# ADC_Analog_Input_Scaler_UPDATED2018.net
KiCad netlist of a schematic drawn in EAGLE
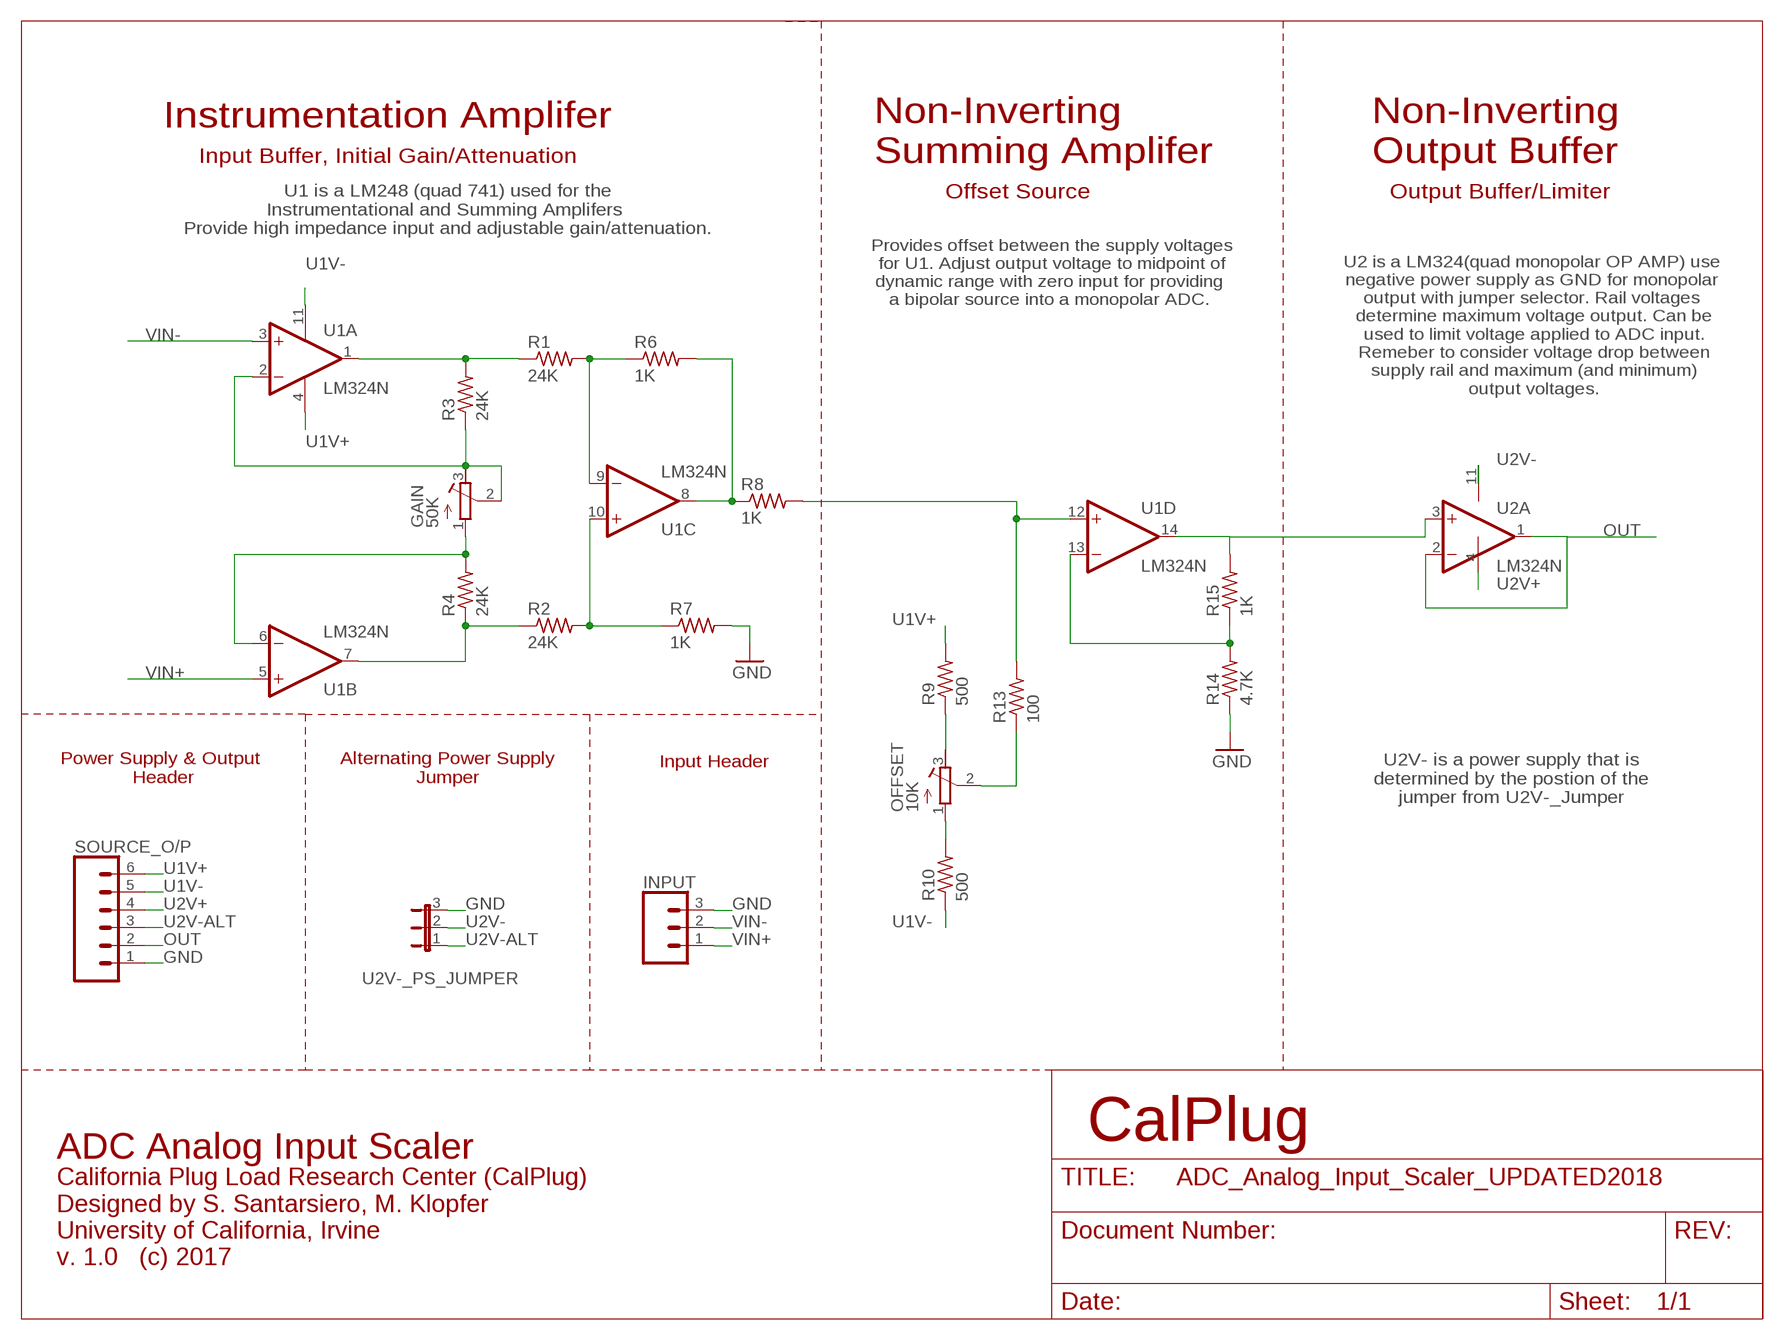
[diagram p0: schematic, sheet 1]

(export (version "E")
  (design (tool "Eeschema 10.0.6"))
  (components
    (comp (ref "GAIN")
      (value "50K")
      (footprint "eagle-import:RTRIM3296W")
      (libsource (lib "eagle-import") (part "R-TRIMM3296W"))
    )
    (comp (ref "INPUT")
      (value "CONN_03")
      (footprint "eagle-import:1X03")
      (libsource (lib "eagle-import") (part "CONN_03"))
    )
    (comp (ref "OFFSET")
      (value "10K")
      (footprint "eagle-import:RTRIM3296W")
      (libsource (lib "eagle-import") (part "R-TRIMM3296W"))
    )
    (comp (ref "R1")
      (value "24K")
      (footprint "eagle-import:R1210")
      (libsource (lib "eagle-import") (part "R-US_R1210"))
    )
    (comp (ref "R2")
      (value "24K")
      (footprint "eagle-import:R1210")
      (libsource (lib "eagle-import") (part "R-US_R1210"))
    )
    (comp (ref "R3")
      (value "24K")
      (footprint "eagle-import:R1210")
      (libsource (lib "eagle-import") (part "R-US_R1210"))
    )
    (comp (ref "R4")
      (value "24K")
      (footprint "eagle-import:R1210")
      (libsource (lib "eagle-import") (part "R-US_R1210"))
    )
    (comp (ref "R6")
      (value "1K")
      (footprint "eagle-import:R1210")
      (libsource (lib "eagle-import") (part "R-US_R1210"))
    )
    (comp (ref "R7")
      (value "1K")
      (footprint "eagle-import:R1210")
      (libsource (lib "eagle-import") (part "R-US_R1210"))
    )
    (comp (ref "R8")
      (value "1K")
      (footprint "eagle-import:R1210")
      (libsource (lib "eagle-import") (part "R-US_R1210"))
    )
    (comp (ref "R9")
      (value "500")
      (footprint "eagle-import:R1206")
      (libsource (lib "eagle-import") (part "R-US_R1206"))
    )
    (comp (ref "R10")
      (value "500")
      (footprint "eagle-import:R1206")
      (libsource (lib "eagle-import") (part "R-US_R1206"))
    )
    (comp (ref "R13")
      (value "100")
      (footprint "eagle-import:R1210")
      (libsource (lib "eagle-import") (part "R-US_R1210"))
    )
    (comp (ref "R14")
      (value "4.7K")
      (footprint "eagle-import:R1210")
      (libsource (lib "eagle-import") (part "R-US_R1210"))
    )
    (comp (ref "R15")
      (value "1K")
      (footprint "eagle-import:R1210")
      (libsource (lib "eagle-import") (part "R-US_R1210"))
    )
    (comp (ref "SOURCE_O/P")
      (value "CONN_06LOCK")
      (footprint "eagle-import:1X06_LOCK")
      (libsource (lib "eagle-import") (part "CONN_06LOCK"))
    )
    (comp (ref "U1")
      (value "LM324N")
      (footprint "eagle-import:DIL14")
      (libsource (lib "eagle-import") (part "LM324N"))
    )
    (comp (ref "U2")
      (value "LM324N")
      (footprint "eagle-import:DIL14")
      (libsource (lib "eagle-import") (part "LM324N"))
    )
    (comp (ref "U2V-_PS_JUMPER")
      (value "JP2E")
      (footprint "eagle-import:JP2")
      (libsource (lib "eagle-import") (part "JP2E"))
    )
  )
  (nets
    (net (code "1") (name "/OUT") (class "Default")
      (node (ref "SOURCE_O/P") (pin "2") (pinfunction "2_2") (pintype "passive"))
      (node (ref "U2") (pin "1") (pinfunction "OUT_1") (pintype "output"))
      (node (ref "U2") (pin "2") (pinfunction "-IN_2") (pintype "input"))
    )
    (net (code "2") (name "/U1V+") (class "Default")
      (node (ref "R9") (pin "2") (pinfunction "2_2") (pintype "passive"))
      (node (ref "SOURCE_O/P") (pin "6") (pinfunction "6_6") (pintype "passive"))
      (node (ref "U1") (pin "4") (pinfunction "V+_4") (pintype "power_in"))
    )
    (net (code "3") (name "/U1V-") (class "Default")
      (node (ref "R10") (pin "1") (pinfunction "1_1") (pintype "passive"))
      (node (ref "SOURCE_O/P") (pin "5") (pinfunction "5_5") (pintype "passive"))
      (node (ref "U1") (pin "11") (pinfunction "V-_11") (pintype "power_in"))
    )
    (net (code "4") (name "/U2V+") (class "Default")
      (node (ref "SOURCE_O/P") (pin "4") (pinfunction "4_4") (pintype "passive"))
      (node (ref "U2") (pin "4") (pinfunction "V+_4") (pintype "power_in"))
    )
    (net (code "5") (name "/U2V-") (class "Default")
      (node (ref "U2") (pin "11") (pinfunction "V-_11") (pintype "power_in"))
      (node (ref "U2V-_PS_JUMPER") (pin "2") (pinfunction "2_2") (pintype "passive"))
    )
    (net (code "6") (name "/U2V-ALT") (class "Default")
      (node (ref "SOURCE_O/P") (pin "3") (pinfunction "3_3") (pintype "passive"))
      (node (ref "U2V-_PS_JUMPER") (pin "1") (pinfunction "1_1") (pintype "passive"))
    )
    (net (code "7") (name "/VIN+") (class "Default")
      (node (ref "INPUT") (pin "1") (pinfunction "1_1") (pintype "passive"))
      (node (ref "U1") (pin "5") (pinfunction "+IN_5") (pintype "input"))
    )
    (net (code "8") (name "/VIN-") (class "Default")
      (node (ref "INPUT") (pin "2") (pinfunction "2_2") (pintype "passive"))
      (node (ref "U1") (pin "3") (pinfunction "+IN_3") (pintype "input"))
    )
    (net (code "9") (name "GND") (class "Default")
      (node (ref "INPUT") (pin "3") (pinfunction "3_3") (pintype "passive"))
      (node (ref "R14") (pin "1") (pinfunction "1_1") (pintype "passive"))
      (node (ref "R7") (pin "2") (pinfunction "2_2") (pintype "passive"))
      (node (ref "SOURCE_O/P") (pin "1") (pinfunction "1_1") (pintype "passive"))
      (node (ref "U2V-_PS_JUMPER") (pin "3") (pinfunction "3_3") (pintype "passive"))
    )
    (net (code "10") (name "Net-(GAIN-A)") (class "Default")
      (node (ref "GAIN") (pin "1") (pinfunction "A_1") (pintype "passive"))
      (node (ref "R4") (pin "2") (pinfunction "2_2") (pintype "passive"))
      (node (ref "U1") (pin "6") (pinfunction "-IN_6") (pintype "input"))
    )
    (net (code "11") (name "Net-(GAIN-E)") (class "Default")
      (node (ref "GAIN") (pin "2") (pinfunction "S_2") (pintype "passive"))
      (node (ref "GAIN") (pin "3") (pinfunction "E_3") (pintype "passive"))
      (node (ref "R3") (pin "1") (pinfunction "1_1") (pintype "passive"))
      (node (ref "U1") (pin "2") (pinfunction "-IN_2") (pintype "input"))
    )
    (net (code "12") (name "Net-(OFFSET-A)") (class "Default")
      (node (ref "OFFSET") (pin "1") (pinfunction "A_1") (pintype "passive"))
      (node (ref "R10") (pin "2") (pinfunction "2_2") (pintype "passive"))
    )
    (net (code "13") (name "Net-(OFFSET-E)") (class "Default")
      (node (ref "OFFSET") (pin "3") (pinfunction "E_3") (pintype "passive"))
      (node (ref "R9") (pin "1") (pinfunction "1_1") (pintype "passive"))
    )
    (net (code "14") (name "Net-(OFFSET-S)") (class "Default")
      (node (ref "OFFSET") (pin "2") (pinfunction "S_2") (pintype "passive"))
      (node (ref "R13") (pin "1") (pinfunction "1_1") (pintype "passive"))
    )
    (net (code "15") (name "Net-(U1A-OUT)") (class "Default")
      (node (ref "R1") (pin "1") (pinfunction "1_1") (pintype "passive"))
      (node (ref "R3") (pin "2") (pinfunction "2_2") (pintype "passive"))
      (node (ref "U1") (pin "1") (pinfunction "OUT_1") (pintype "output"))
    )
    (net (code "16") (name "Net-(U1B-OUT)") (class "Default")
      (node (ref "R2") (pin "1") (pinfunction "1_1") (pintype "passive"))
      (node (ref "R4") (pin "1") (pinfunction "1_1") (pintype "passive"))
      (node (ref "U1") (pin "7") (pinfunction "OUT_7") (pintype "output"))
    )
    (net (code "17") (name "Net-(U1C-+IN)") (class "Default")
      (node (ref "R2") (pin "2") (pinfunction "2_2") (pintype "passive"))
      (node (ref "R7") (pin "1") (pinfunction "1_1") (pintype "passive"))
      (node (ref "U1") (pin "10") (pinfunction "+IN_10") (pintype "input"))
    )
    (net (code "18") (name "Net-(U1C--IN)") (class "Default")
      (node (ref "R1") (pin "2") (pinfunction "2_2") (pintype "passive"))
      (node (ref "R6") (pin "1") (pinfunction "1_1") (pintype "passive"))
      (node (ref "U1") (pin "9") (pinfunction "-IN_9") (pintype "input"))
    )
    (net (code "19") (name "Net-(U1C-OUT)") (class "Default")
      (node (ref "R6") (pin "2") (pinfunction "2_2") (pintype "passive"))
      (node (ref "R8") (pin "1") (pinfunction "1_1") (pintype "passive"))
      (node (ref "U1") (pin "8") (pinfunction "OUT_8") (pintype "output"))
    )
    (net (code "20") (name "Net-(U1D-+IN)") (class "Default")
      (node (ref "R13") (pin "2") (pinfunction "2_2") (pintype "passive"))
      (node (ref "R8") (pin "2") (pinfunction "2_2") (pintype "passive"))
      (node (ref "U1") (pin "12") (pinfunction "+IN_12") (pintype "input"))
    )
    (net (code "21") (name "Net-(U1D--IN)") (class "Default")
      (node (ref "R14") (pin "2") (pinfunction "2_2") (pintype "passive"))
      (node (ref "R15") (pin "1") (pinfunction "1_1") (pintype "passive"))
      (node (ref "U1") (pin "13") (pinfunction "-IN_13") (pintype "input"))
    )
    (net (code "22") (name "Net-(U1D-OUT)") (class "Default")
      (node (ref "R15") (pin "2") (pinfunction "2_2") (pintype "passive"))
      (node (ref "U1") (pin "14") (pinfunction "OUT_14") (pintype "output"))
      (node (ref "U2") (pin "3") (pinfunction "+IN_3") (pintype "input"))
    )
  )
)
